# Drivers.net
KiCad netlist of a schematic drawn in Altium Designer
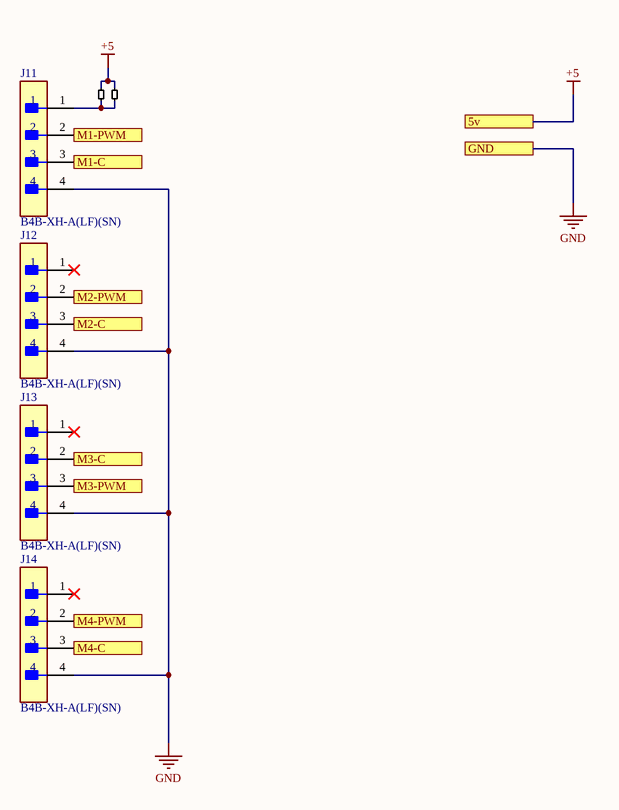
[diagram p0: Drivers.SchDoc]

(export (version "E")
  (design (tool "Eeschema 10.0.6"))
  (components
    (comp (ref "J11")
      (value "B4B-XH-A(LF)(SN)")
      (footprint "FP-B4B-XH-A_LF_SN-MFG")
      (description "CONN HEADER VERT 4POS 2.5MM")
      (libsource (lib "Altium Content Vault") (part "299a8cea1bdcbc3624fe62c390fa72c"))
    )
    (comp (ref "J12")
      (value "B4B-XH-A(LF)(SN)")
      (footprint "FP-B4B-XH-A_LF_SN-MFG")
      (description "CONN HEADER VERT 4POS 2.5MM")
      (libsource (lib "Altium Content Vault") (part "299a8cea1bdcbc3624fe62c390fa72c"))
    )
    (comp (ref "J13")
      (value "B4B-XH-A(LF)(SN)")
      (footprint "FP-B4B-XH-A_LF_SN-MFG")
      (description "CONN HEADER VERT 4POS 2.5MM")
      (libsource (lib "Altium Content Vault") (part "299a8cea1bdcbc3624fe62c390fa72c"))
    )
    (comp (ref "J14")
      (value "B4B-XH-A(LF)(SN)")
      (footprint "FP-B4B-XH-A_LF_SN-MFG")
      (description "CONN HEADER VERT 4POS 2.5MM")
      (libsource (lib "Altium Content Vault") (part "299a8cea1bdcbc3624fe62c390fa72c"))
    )
    (comp (ref "W30") (value "Jumper") (footprint "Jumper Mid") (libsource (lib "Schlib1") (part "Jumper")))
    (comp (ref "W31") (value "Jumper") (footprint "Jumper Mid") (libsource (lib "Schlib1") (part "Jumper")))
  )
  (nets
    (net (code "1") (name "+5") (class "Default")
      (node (ref "W30") (pin "2") (pinfunction "2_2") (pintype "passive"))
      (node (ref "W31") (pin "2") (pinfunction "2_2") (pintype "passive"))
    )
    (net (code "2") (name "/M1-C") (class "Default")
      (node (ref "J11") (pin "3") (pinfunction "3_3") (pintype "passive"))
    )
    (net (code "3") (name "/M1-PWM") (class "Default")
      (node (ref "J11") (pin "2") (pinfunction "2_2") (pintype "passive"))
    )
    (net (code "4") (name "/M2-C") (class "Default")
      (node (ref "J12") (pin "3") (pinfunction "3_3") (pintype "passive"))
    )
    (net (code "5") (name "/M2-PWM") (class "Default")
      (node (ref "J12") (pin "2") (pinfunction "2_2") (pintype "passive"))
    )
    (net (code "6") (name "/M3-C") (class "Default")
      (node (ref "J13") (pin "2") (pinfunction "2_2") (pintype "passive"))
    )
    (net (code "7") (name "/M3-PWM") (class "Default")
      (node (ref "J13") (pin "3") (pinfunction "3_3") (pintype "passive"))
    )
    (net (code "8") (name "/M4-C") (class "Default")
      (node (ref "J14") (pin "3") (pinfunction "3_3") (pintype "passive"))
    )
    (net (code "9") (name "/M4-PWM") (class "Default")
      (node (ref "J14") (pin "2") (pinfunction "2_2") (pintype "passive"))
    )
    (net (code "10") (name "GND") (class "Default")
      (node (ref "J11") (pin "4") (pinfunction "4_4") (pintype "passive"))
      (node (ref "J12") (pin "4") (pinfunction "4_4") (pintype "passive"))
      (node (ref "J13") (pin "4") (pinfunction "4_4") (pintype "passive"))
      (node (ref "J14") (pin "4") (pinfunction "4_4") (pintype "passive"))
    )
    (net (code "11") (name "Net-(J11-Pad1)") (class "Default")
      (node (ref "J11") (pin "1") (pinfunction "1_1") (pintype "passive"))
      (node (ref "W30") (pin "1") (pinfunction "1_1") (pintype "passive"))
      (node (ref "W31") (pin "1") (pinfunction "1_1") (pintype "passive"))
    )
    (net (code "12") (name "unconnected-(J12-Pad1)") (class "Default")
      (node (ref "J12") (pin "1") (pinfunction "1_1") (pintype "passive+no_connect"))
    )
    (net (code "13") (name "unconnected-(J13-Pad1)") (class "Default")
      (node (ref "J13") (pin "1") (pinfunction "1_1") (pintype "passive+no_connect"))
    )
    (net (code "14") (name "unconnected-(J14-Pad1)") (class "Default")
      (node (ref "J14") (pin "1") (pinfunction "1_1") (pintype "passive+no_connect"))
    )
  )
)
